# fpga_power.net
KiCad netlist of a schematic drawn in Altium Designer
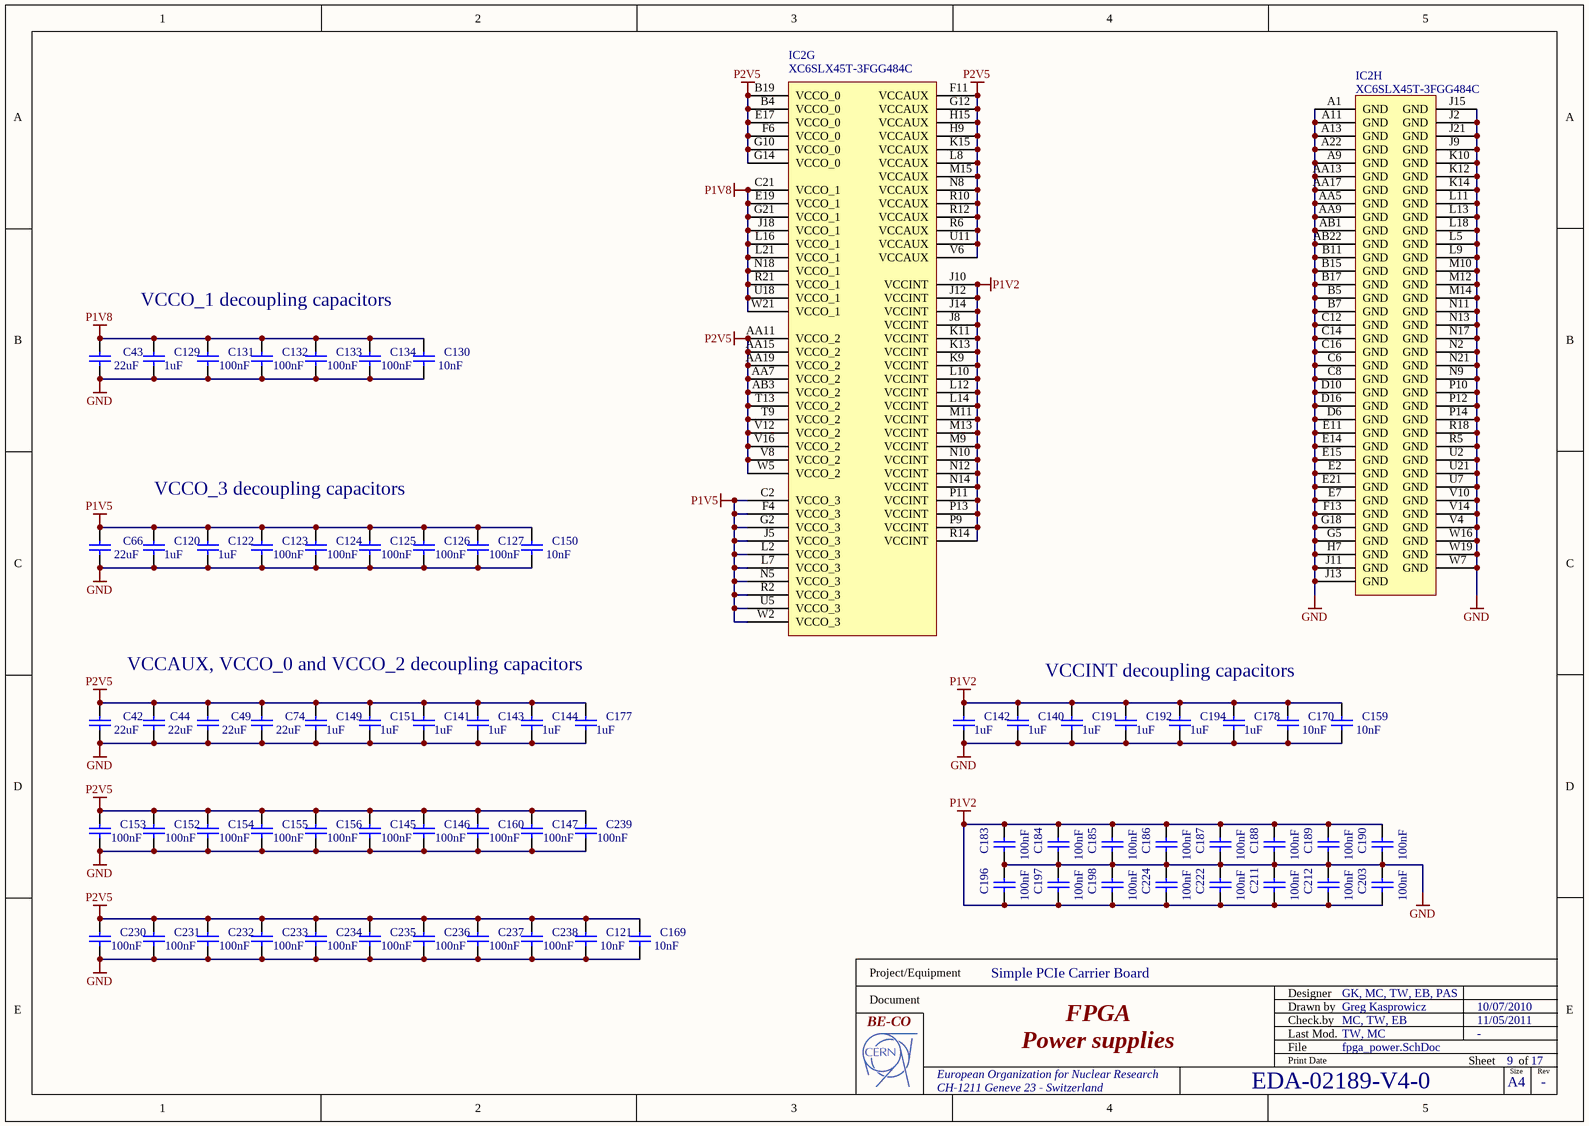
[diagram p0: fpga_power.SchDoc]

(export (version "E")
  (design (tool "Eeschema 10.0.6"))
  (components
    (comp (ref "C42")
      (value "22uF")
      (footprint "CAPC3216X180N")
      (description "Non-polarised capacitor")
      (fields
        (field (name "PART NUMBER") "CC1206_22UF_10V_10%_X7R")
        (field (name "VOLTAGE") "10V")
        (field (name "AUTHOR") "CERN DEM JLC")
      )
      (libsource (lib "Capacitors") (part "Capacitor - non polarized"))
    )
    (comp (ref "C43")
      (value "22uF")
      (footprint "CAPC3216X180N")
      (description "Non-polarised capacitor")
      (fields
        (field (name "PART NUMBER") "CC1206_22UF_10V_10%_X7R")
        (field (name "VOLTAGE") "10V")
        (field (name "AUTHOR") "CERN DEM JLC")
      )
      (libsource (lib "Capacitors") (part "Capacitor - non polarized"))
    )
    (comp (ref "C44")
      (value "22uF")
      (footprint "CAPC3216X180N")
      (description "Non-polarised capacitor")
      (fields
        (field (name "PART NUMBER") "CC1206_22UF_10V_10%_X7R")
        (field (name "VOLTAGE") "10V")
        (field (name "AUTHOR") "CERN DEM JLC")
      )
      (libsource (lib "Capacitors") (part "Capacitor - non polarized"))
    )
    (comp (ref "C49")
      (value "22uF")
      (footprint "CAPC3216X180N")
      (description "Non-polarised capacitor")
      (fields
        (field (name "PART NUMBER") "CC1206_22UF_10V_10%_X7R")
        (field (name "VOLTAGE") "10V")
        (field (name "AUTHOR") "CERN DEM JLC")
      )
      (libsource (lib "Capacitors") (part "Capacitor - non polarized"))
    )
    (comp (ref "C66")
      (value "22uF")
      (footprint "CAPC3216X180N")
      (description "Non-polarised capacitor")
      (fields
        (field (name "PART NUMBER") "CC1206_22UF_10V_10%_X7R")
        (field (name "VOLTAGE") "10V")
        (field (name "AUTHOR") "CERN DEM JLC")
      )
      (libsource (lib "Capacitors") (part "Capacitor - non polarized"))
    )
    (comp (ref "C74")
      (value "22uF")
      (footprint "CAPC3216X180N")
      (description "Non-polarised capacitor")
      (fields
        (field (name "PART NUMBER") "CC1206_22UF_10V_10%_X7R")
        (field (name "VOLTAGE") "10V")
        (field (name "AUTHOR") "CERN DEM JLC")
      )
      (libsource (lib "Capacitors") (part "Capacitor - non polarized"))
    )
    (comp (ref "C120")
      (value "1uF")
      (footprint "CAPC1608X87N")
      (description "Non-polarised capacitor")
      (fields
        (field (name "PART NUMBER") "CC0603_1UF_16V_10%_X7R")
        (field (name "VOLTAGE") "16V")
        (field (name "AUTHOR") "CERN DEM JLC")
      )
      (libsource (lib "Capacitors") (part "Capacitor - non polarized"))
    )
    (comp (ref "C121")
      (value "10nF")
      (footprint "CAPC1608X87N")
      (description "Non-polarised capacitor")
      (fields
        (field (name "PART NUMBER") "CC0603_10NF_50V_10%_X7R")
        (field (name "VOLTAGE") "50V")
        (field (name "AUTHOR") "CERN DEM JLC")
      )
      (libsource (lib "Capacitors") (part "Capacitor - non polarized"))
    )
    (comp (ref "C122")
      (value "1uF")
      (footprint "CAPC1608X87N")
      (description "Non-polarised capacitor")
      (fields
        (field (name "PART NUMBER") "CC0603_1UF_16V_10%_X7R")
        (field (name "VOLTAGE") "16V")
        (field (name "AUTHOR") "CERN DEM JLC")
      )
      (libsource (lib "Capacitors") (part "Capacitor - non polarized"))
    )
    (comp (ref "C123")
      (value "100nF")
      (footprint "CAPC1005X55N")
      (description "Non-polarised capacitor")
      (fields
        (field (name "PART NUMBER") "CC0402_100NF_16V_10%_X7R")
        (field (name "VOLTAGE") "16V")
        (field (name "AUTHOR") "CERN DEM JLC")
      )
      (libsource (lib "Capacitors") (part "Capacitor - non polarized"))
    )
    (comp (ref "C124")
      (value "100nF")
      (footprint "CAPC1005X55N")
      (description "Non-polarised capacitor")
      (fields
        (field (name "PART NUMBER") "CC0402_100NF_16V_10%_X7R")
        (field (name "VOLTAGE") "16V")
        (field (name "AUTHOR") "CERN DEM JLC")
      )
      (libsource (lib "Capacitors") (part "Capacitor - non polarized"))
    )
    (comp (ref "C125")
      (value "100nF")
      (footprint "CAPC1005X55N")
      (description "Non-polarised capacitor")
      (fields
        (field (name "PART NUMBER") "CC0402_100NF_16V_10%_X7R")
        (field (name "VOLTAGE") "16V")
        (field (name "AUTHOR") "CERN DEM JLC")
      )
      (libsource (lib "Capacitors") (part "Capacitor - non polarized"))
    )
    (comp (ref "C126")
      (value "100nF")
      (footprint "CAPC1005X55N")
      (description "Non-polarised capacitor")
      (fields
        (field (name "PART NUMBER") "CC0402_100NF_16V_10%_X7R")
        (field (name "VOLTAGE") "16V")
        (field (name "AUTHOR") "CERN DEM JLC")
      )
      (libsource (lib "Capacitors") (part "Capacitor - non polarized"))
    )
    (comp (ref "C127")
      (value "100nF")
      (footprint "CAPC1005X55N")
      (description "Non-polarised capacitor")
      (fields
        (field (name "PART NUMBER") "CC0402_100NF_16V_10%_X7R")
        (field (name "VOLTAGE") "16V")
        (field (name "AUTHOR") "CERN DEM JLC")
      )
      (libsource (lib "Capacitors") (part "Capacitor - non polarized"))
    )
    (comp (ref "C129")
      (value "1uF")
      (footprint "CAPC1608X87N")
      (description "Non-polarised capacitor")
      (fields
        (field (name "PART NUMBER") "CC0603_1UF_16V_10%_X7R")
        (field (name "VOLTAGE") "16V")
        (field (name "AUTHOR") "CERN DEM JLC")
      )
      (libsource (lib "Capacitors") (part "Capacitor - non polarized"))
    )
    (comp (ref "C130")
      (value "10nF")
      (footprint "CAPC1608X87N")
      (description "Non-polarised capacitor")
      (fields
        (field (name "PART NUMBER") "CC0603_10NF_50V_10%_X7R")
        (field (name "VOLTAGE") "50V")
        (field (name "AUTHOR") "CERN DEM JLC")
      )
      (libsource (lib "Capacitors") (part "Capacitor - non polarized"))
    )
    (comp (ref "C131")
      (value "100nF")
      (footprint "CAPC1005X55N")
      (description "Non-polarised capacitor")
      (fields
        (field (name "PART NUMBER") "CC0402_100NF_16V_10%_X7R")
        (field (name "VOLTAGE") "16V")
        (field (name "AUTHOR") "CERN DEM JLC")
      )
      (libsource (lib "Capacitors") (part "Capacitor - non polarized"))
    )
    (comp (ref "C132")
      (value "100nF")
      (footprint "CAPC1005X55N")
      (description "Non-polarised capacitor")
      (fields
        (field (name "PART NUMBER") "CC0402_100NF_16V_10%_X7R")
        (field (name "VOLTAGE") "16V")
        (field (name "AUTHOR") "CERN DEM JLC")
      )
      (libsource (lib "Capacitors") (part "Capacitor - non polarized"))
    )
    (comp (ref "C133")
      (value "100nF")
      (footprint "CAPC1005X55N")
      (description "Non-polarised capacitor")
      (fields
        (field (name "PART NUMBER") "CC0402_100NF_16V_10%_X7R")
        (field (name "VOLTAGE") "16V")
        (field (name "AUTHOR") "CERN DEM JLC")
      )
      (libsource (lib "Capacitors") (part "Capacitor - non polarized"))
    )
    (comp (ref "C134")
      (value "100nF")
      (footprint "CAPC1005X55N")
      (description "Non-polarised capacitor")
      (fields
        (field (name "PART NUMBER") "CC0402_100NF_16V_10%_X7R")
        (field (name "VOLTAGE") "16V")
        (field (name "AUTHOR") "CERN DEM JLC")
      )
      (libsource (lib "Capacitors") (part "Capacitor - non polarized"))
    )
    (comp (ref "C140")
      (value "1uF")
      (footprint "CAPC1608X87N")
      (description "Non-polarised capacitor")
      (fields
        (field (name "PART NUMBER") "CC0603_1UF_16V_10%_X7R")
        (field (name "VOLTAGE") "16V")
        (field (name "AUTHOR") "CERN DEM JLC")
      )
      (libsource (lib "Capacitors") (part "Capacitor - non polarized"))
    )
    (comp (ref "C141")
      (value "1uF")
      (footprint "CAPC1608X87N")
      (description "Non-polarised capacitor")
      (fields
        (field (name "PART NUMBER") "CC0603_1UF_16V_10%_X7R")
        (field (name "VOLTAGE") "16V")
        (field (name "AUTHOR") "CERN DEM JLC")
      )
      (libsource (lib "Capacitors") (part "Capacitor - non polarized"))
    )
    (comp (ref "C142")
      (value "1uF")
      (footprint "CAPC1608X87N")
      (description "Non-polarised capacitor")
      (fields
        (field (name "PART NUMBER") "CC0603_1UF_16V_10%_X7R")
        (field (name "VOLTAGE") "16V")
        (field (name "AUTHOR") "CERN DEM JLC")
      )
      (libsource (lib "Capacitors") (part "Capacitor - non polarized"))
    )
    (comp (ref "C143")
      (value "1uF")
      (footprint "CAPC1608X87N")
      (description "Non-polarised capacitor")
      (fields
        (field (name "PART NUMBER") "CC0603_1UF_16V_10%_X7R")
        (field (name "VOLTAGE") "16V")
        (field (name "AUTHOR") "CERN DEM JLC")
      )
      (libsource (lib "Capacitors") (part "Capacitor - non polarized"))
    )
    (comp (ref "C144")
      (value "1uF")
      (footprint "CAPC1608X87N")
      (description "Non-polarised capacitor")
      (fields
        (field (name "PART NUMBER") "CC0603_1UF_16V_10%_X7R")
        (field (name "VOLTAGE") "16V")
        (field (name "AUTHOR") "CERN DEM JLC")
      )
      (libsource (lib "Capacitors") (part "Capacitor - non polarized"))
    )
    (comp (ref "C145")
      (value "100nF")
      (footprint "CAPC1005X55N")
      (description "Non-polarised capacitor")
      (fields
        (field (name "PART NUMBER") "CC0402_100NF_16V_10%_X7R")
        (field (name "VOLTAGE") "16V")
        (field (name "AUTHOR") "CERN DEM JLC")
      )
      (libsource (lib "Capacitors") (part "Capacitor - non polarized"))
    )
    (comp (ref "C146")
      (value "100nF")
      (footprint "CAPC1005X55N")
      (description "Non-polarised capacitor")
      (fields
        (field (name "PART NUMBER") "CC0402_100NF_16V_10%_X7R")
        (field (name "VOLTAGE") "16V")
        (field (name "AUTHOR") "CERN DEM JLC")
      )
      (libsource (lib "Capacitors") (part "Capacitor - non polarized"))
    )
    (comp (ref "C147")
      (value "100nF")
      (footprint "CAPC1005X55N")
      (description "Non-polarised capacitor")
      (fields
        (field (name "PART NUMBER") "CC0402_100NF_16V_10%_X7R")
        (field (name "VOLTAGE") "16V")
        (field (name "AUTHOR") "CERN DEM JLC")
      )
      (libsource (lib "Capacitors") (part "Capacitor - non polarized"))
    )
    (comp (ref "C149")
      (value "1uF")
      (footprint "CAPC1608X87N")
      (description "Non-polarised capacitor")
      (fields
        (field (name "PART NUMBER") "CC0603_1UF_16V_10%_X7R")
        (field (name "VOLTAGE") "16V")
        (field (name "AUTHOR") "CERN DEM JLC")
      )
      (libsource (lib "Capacitors") (part "Capacitor - non polarized"))
    )
    (comp (ref "C150")
      (value "10nF")
      (footprint "CAPC1608X87N")
      (description "Non-polarised capacitor")
      (fields
        (field (name "PART NUMBER") "CC0603_10NF_50V_10%_X7R")
        (field (name "VOLTAGE") "50V")
        (field (name "AUTHOR") "CERN DEM JLC")
      )
      (libsource (lib "Capacitors") (part "Capacitor - non polarized"))
    )
    (comp (ref "C151")
      (value "1uF")
      (footprint "CAPC1608X87N")
      (description "Non-polarised capacitor")
      (fields
        (field (name "PART NUMBER") "CC0603_1UF_16V_10%_X7R")
        (field (name "VOLTAGE") "16V")
        (field (name "AUTHOR") "CERN DEM JLC")
      )
      (libsource (lib "Capacitors") (part "Capacitor - non polarized"))
    )
    (comp (ref "C152")
      (value "100nF")
      (footprint "CAPC1005X55N")
      (description "Non-polarised capacitor")
      (fields
        (field (name "PART NUMBER") "CC0402_100NF_16V_10%_X7R")
        (field (name "VOLTAGE") "16V")
        (field (name "AUTHOR") "CERN DEM JLC")
      )
      (libsource (lib "Capacitors") (part "Capacitor - non polarized"))
    )
    (comp (ref "C153")
      (value "100nF")
      (footprint "CAPC1005X55N")
      (description "Non-polarised capacitor")
      (fields
        (field (name "PART NUMBER") "CC0402_100NF_16V_10%_X7R")
        (field (name "VOLTAGE") "16V")
        (field (name "AUTHOR") "CERN DEM JLC")
      )
      (libsource (lib "Capacitors") (part "Capacitor - non polarized"))
    )
    (comp (ref "C154")
      (value "100nF")
      (footprint "CAPC1005X55N")
      (description "Non-polarised capacitor")
      (fields
        (field (name "PART NUMBER") "CC0402_100NF_16V_10%_X7R")
        (field (name "VOLTAGE") "16V")
        (field (name "AUTHOR") "CERN DEM JLC")
      )
      (libsource (lib "Capacitors") (part "Capacitor - non polarized"))
    )
    (comp (ref "C155")
      (value "100nF")
      (footprint "CAPC1005X55N")
      (description "Non-polarised capacitor")
      (fields
        (field (name "PART NUMBER") "CC0402_100NF_16V_10%_X7R")
        (field (name "VOLTAGE") "16V")
        (field (name "AUTHOR") "CERN DEM JLC")
      )
      (libsource (lib "Capacitors") (part "Capacitor - non polarized"))
    )
    (comp (ref "C156")
      (value "100nF")
      (footprint "CAPC1005X55N")
      (description "Non-polarised capacitor")
      (fields
        (field (name "PART NUMBER") "CC0402_100NF_16V_10%_X7R")
        (field (name "VOLTAGE") "16V")
        (field (name "AUTHOR") "CERN DEM JLC")
      )
      (libsource (lib "Capacitors") (part "Capacitor - non polarized"))
    )
    (comp (ref "C159")
      (value "10nF")
      (footprint "CAPC1608X87N")
      (description "Non-polarised capacitor")
      (fields
        (field (name "PART NUMBER") "CC0603_10NF_50V_10%_X7R")
        (field (name "VOLTAGE") "50V")
        (field (name "AUTHOR") "CERN DEM JLC")
      )
      (libsource (lib "Capacitors") (part "Capacitor - non polarized"))
    )
    (comp (ref "C160")
      (value "100nF")
      (footprint "CAPC1005X55N")
      (description "Non-polarised capacitor")
      (fields
        (field (name "PART NUMBER") "CC0402_100NF_16V_10%_X7R")
        (field (name "VOLTAGE") "16V")
        (field (name "AUTHOR") "CERN DEM JLC")
      )
      (libsource (lib "Capacitors") (part "Capacitor - non polarized"))
    )
    (comp (ref "C169")
      (value "10nF")
      (footprint "CAPC1608X87N")
      (description "Non-polarised capacitor")
      (fields
        (field (name "PART NUMBER") "CC0603_10NF_50V_10%_X7R")
        (field (name "VOLTAGE") "50V")
        (field (name "AUTHOR") "CERN DEM JLC")
      )
      (libsource (lib "Capacitors") (part "Capacitor - non polarized"))
    )
    (comp (ref "C170")
      (value "10nF")
      (footprint "CAPC1608X87N")
      (description "Non-polarised capacitor")
      (fields
        (field (name "PART NUMBER") "CC0603_10NF_50V_10%_X7R")
        (field (name "VOLTAGE") "50V")
        (field (name "AUTHOR") "CERN DEM JLC")
      )
      (libsource (lib "Capacitors") (part "Capacitor - non polarized"))
    )
    (comp (ref "C177")
      (value "1uF")
      (footprint "CAPC1608X87N")
      (description "Non-polarised capacitor")
      (fields
        (field (name "PART NUMBER") "CC0603_1UF_16V_10%_X7R")
        (field (name "VOLTAGE") "16V")
        (field (name "AUTHOR") "CERN DEM JLC")
      )
      (libsource (lib "Capacitors") (part "Capacitor - non polarized"))
    )
    (comp (ref "C178")
      (value "1uF")
      (footprint "CAPC1608X87N")
      (description "Non-polarised capacitor")
      (fields
        (field (name "PART NUMBER") "CC0603_1UF_16V_10%_X7R")
        (field (name "VOLTAGE") "16V")
        (field (name "AUTHOR") "CERN DEM JLC")
      )
      (libsource (lib "Capacitors") (part "Capacitor - non polarized"))
    )
    (comp (ref "C183")
      (value "100nF")
      (footprint "CAPC1005X55N")
      (description "Non-polarised capacitor")
      (fields
        (field (name "PART NUMBER") "CC0402_100NF_16V_10%_X7R")
        (field (name "VOLTAGE") "16V")
        (field (name "AUTHOR") "CERN DEM JLC")
      )
      (libsource (lib "Capacitors") (part "Capacitor - non polarized"))
    )
    (comp (ref "C184")
      (value "100nF")
      (footprint "CAPC1005X55N")
      (description "Non-polarised capacitor")
      (fields
        (field (name "PART NUMBER") "CC0402_100NF_16V_10%_X7R")
        (field (name "VOLTAGE") "16V")
        (field (name "AUTHOR") "CERN DEM JLC")
      )
      (libsource (lib "Capacitors") (part "Capacitor - non polarized"))
    )
    (comp (ref "C185")
      (value "100nF")
      (footprint "CAPC1005X55N")
      (description "Non-polarised capacitor")
      (fields
        (field (name "PART NUMBER") "CC0402_100NF_16V_10%_X7R")
        (field (name "VOLTAGE") "16V")
        (field (name "AUTHOR") "CERN DEM JLC")
      )
      (libsource (lib "Capacitors") (part "Capacitor - non polarized"))
    )
    (comp (ref "C186")
      (value "100nF")
      (footprint "CAPC1005X55N")
      (description "Non-polarised capacitor")
      (fields
        (field (name "PART NUMBER") "CC0402_100NF_16V_10%_X7R")
        (field (name "VOLTAGE") "16V")
        (field (name "AUTHOR") "CERN DEM JLC")
      )
      (libsource (lib "Capacitors") (part "Capacitor - non polarized"))
    )
    (comp (ref "C187")
      (value "100nF")
      (footprint "CAPC1005X55N")
      (description "Non-polarised capacitor")
      (fields
        (field (name "PART NUMBER") "CC0402_100NF_16V_10%_X7R")
        (field (name "VOLTAGE") "16V")
        (field (name "AUTHOR") "CERN DEM JLC")
      )
      (libsource (lib "Capacitors") (part "Capacitor - non polarized"))
    )
    (comp (ref "C188")
      (value "100nF")
      (footprint "CAPC1005X55N")
      (description "Non-polarised capacitor")
      (fields
        (field (name "PART NUMBER") "CC0402_100NF_16V_10%_X7R")
        (field (name "VOLTAGE") "16V")
        (field (name "AUTHOR") "CERN DEM JLC")
      )
      (libsource (lib "Capacitors") (part "Capacitor - non polarized"))
    )
    (comp (ref "C189")
      (value "100nF")
      (footprint "CAPC1005X55N")
      (description "Non-polarised capacitor")
      (fields
        (field (name "PART NUMBER") "CC0402_100NF_16V_10%_X7R")
        (field (name "VOLTAGE") "16V")
        (field (name "AUTHOR") "CERN DEM JLC")
      )
      (libsource (lib "Capacitors") (part "Capacitor - non polarized"))
    )
    (comp (ref "C190")
      (value "100nF")
      (footprint "CAPC1005X55N")
      (description "Non-polarised capacitor")
      (fields
        (field (name "PART NUMBER") "CC0402_100NF_16V_10%_X7R")
        (field (name "VOLTAGE") "16V")
        (field (name "AUTHOR") "CERN DEM JLC")
      )
      (libsource (lib "Capacitors") (part "Capacitor - non polarized"))
    )
    (comp (ref "C191")
      (value "1uF")
      (footprint "CAPC1608X87N")
      (description "Non-polarised capacitor")
      (fields
        (field (name "PART NUMBER") "CC0603_1UF_16V_10%_X7R")
        (field (name "VOLTAGE") "16V")
        (field (name "AUTHOR") "CERN DEM JLC")
      )
      (libsource (lib "Capacitors") (part "Capacitor - non polarized"))
    )
    (comp (ref "C192")
      (value "1uF")
      (footprint "CAPC1608X87N")
      (description "Non-polarised capacitor")
      (fields
        (field (name "PART NUMBER") "CC0603_1UF_16V_10%_X7R")
        (field (name "VOLTAGE") "16V")
        (field (name "AUTHOR") "CERN DEM JLC")
      )
      (libsource (lib "Capacitors") (part "Capacitor - non polarized"))
    )
    (comp (ref "C194")
      (value "1uF")
      (footprint "CAPC1608X87N")
      (description "Non-polarised capacitor")
      (fields
        (field (name "PART NUMBER") "CC0603_1UF_16V_10%_X7R")
        (field (name "VOLTAGE") "16V")
        (field (name "AUTHOR") "CERN DEM JLC")
      )
      (libsource (lib "Capacitors") (part "Capacitor - non polarized"))
    )
    (comp (ref "C196")
      (value "100nF")
      (footprint "CAPC1005X55N")
      (description "Non-polarised capacitor")
      (fields
        (field (name "PART NUMBER") "CC0402_100NF_16V_10%_X7R")
        (field (name "VOLTAGE") "16V")
        (field (name "AUTHOR") "CERN DEM JLC")
      )
      (libsource (lib "Capacitors") (part "Capacitor - non polarized"))
    )
    (comp (ref "C197")
      (value "100nF")
      (footprint "CAPC1005X55N")
      (description "Non-polarised capacitor")
      (fields
        (field (name "PART NUMBER") "CC0402_100NF_16V_10%_X7R")
        (field (name "VOLTAGE") "16V")
        (field (name "AUTHOR") "CERN DEM JLC")
      )
      (libsource (lib "Capacitors") (part "Capacitor - non polarized"))
    )
    (comp (ref "C198")
      (value "100nF")
      (footprint "CAPC1005X55N")
      (description "Non-polarised capacitor")
      (fields
        (field (name "PART NUMBER") "CC0402_100NF_16V_10%_X7R")
        (field (name "VOLTAGE") "16V")
        (field (name "AUTHOR") "CERN DEM JLC")
      )
      (libsource (lib "Capacitors") (part "Capacitor - non polarized"))
    )
    (comp (ref "C203")
      (value "100nF")
      (footprint "CAPC1005X55N")
      (description "Non-polarised capacitor")
      (fields
        (field (name "PART NUMBER") "CC0402_100NF_16V_10%_X7R")
        (field (name "VOLTAGE") "16V")
        (field (name "AUTHOR") "CERN DEM JLC")
      )
      (libsource (lib "Capacitors") (part "Capacitor - non polarized"))
    )
    (comp (ref "C211")
      (value "100nF")
      (footprint "CAPC1005X55N")
      (description "Non-polarised capacitor")
      (fields
        (field (name "PART NUMBER") "CC0402_100NF_16V_10%_X7R")
        (field (name "VOLTAGE") "16V")
        (field (name "AUTHOR") "CERN DEM JLC")
      )
      (libsource (lib "Capacitors") (part "Capacitor - non polarized"))
    )
    (comp (ref "C212")
      (value "100nF")
      (footprint "CAPC1005X55N")
      (description "Non-polarised capacitor")
      (fields
        (field (name "PART NUMBER") "CC0402_100NF_16V_10%_X7R")
        (field (name "VOLTAGE") "16V")
        (field (name "AUTHOR") "CERN DEM JLC")
      )
      (libsource (lib "Capacitors") (part "Capacitor - non polarized"))
    )
    (comp (ref "C222")
      (value "100nF")
      (footprint "CAPC1005X55N")
      (description "Non-polarised capacitor")
      (fields
        (field (name "PART NUMBER") "CC0402_100NF_16V_10%_X7R")
        (field (name "VOLTAGE") "16V")
        (field (name "AUTHOR") "CERN DEM JLC")
      )
      (libsource (lib "Capacitors") (part "Capacitor - non polarized"))
    )
    (comp (ref "C224")
      (value "100nF")
      (footprint "CAPC1005X55N")
      (description "Non-polarised capacitor")
      (fields
        (field (name "PART NUMBER") "CC0402_100NF_16V_10%_X7R")
        (field (name "VOLTAGE") "16V")
        (field (name "AUTHOR") "CERN DEM JLC")
      )
      (libsource (lib "Capacitors") (part "Capacitor - non polarized"))
    )
    (comp (ref "C230")
      (value "100nF")
      (footprint "CAPC1005X55N")
      (description "Non-polarised capacitor")
      (fields
        (field (name "PART NUMBER") "CC0402_100NF_16V_10%_X7R")
        (field (name "VOLTAGE") "16V")
        (field (name "AUTHOR") "CERN DEM JLC")
      )
      (libsource (lib "Capacitors") (part "Capacitor - non polarized"))
    )
    (comp (ref "C231")
      (value "100nF")
      (footprint "CAPC1005X55N")
      (description "Non-polarised capacitor")
      (fields
        (field (name "PART NUMBER") "CC0402_100NF_16V_10%_X7R")
        (field (name "VOLTAGE") "16V")
        (field (name "AUTHOR") "CERN DEM JLC")
      )
      (libsource (lib "Capacitors") (part "Capacitor - non polarized"))
    )
    (comp (ref "C232")
      (value "100nF")
      (footprint "CAPC1005X55N")
      (description "Non-polarised capacitor")
      (fields
        (field (name "PART NUMBER") "CC0402_100NF_16V_10%_X7R")
        (field (name "VOLTAGE") "16V")
        (field (name "AUTHOR") "CERN DEM JLC")
      )
      (libsource (lib "Capacitors") (part "Capacitor - non polarized"))
    )
    (comp (ref "C233")
      (value "100nF")
      (footprint "CAPC1005X55N")
      (description "Non-polarised capacitor")
      (fields
        (field (name "PART NUMBER") "CC0402_100NF_16V_10%_X7R")
        (field (name "VOLTAGE") "16V")
        (field (name "AUTHOR") "CERN DEM JLC")
      )
      (libsource (lib "Capacitors") (part "Capacitor - non polarized"))
    )
    (comp (ref "C234")
      (value "100nF")
      (footprint "CAPC1005X55N")
      (description "Non-polarised capacitor")
      (fields
        (field (name "PART NUMBER") "CC0402_100NF_16V_10%_X7R")
        (field (name "VOLTAGE") "16V")
        (field (name "AUTHOR") "CERN DEM JLC")
      )
      (libsource (lib "Capacitors") (part "Capacitor - non polarized"))
    )
    (comp (ref "C235")
      (value "100nF")
      (footprint "CAPC1005X55N")
      (description "Non-polarised capacitor")
      (fields
        (field (name "PART NUMBER") "CC0402_100NF_16V_10%_X7R")
        (field (name "VOLTAGE") "16V")
        (field (name "AUTHOR") "CERN DEM JLC")
      )
      (libsource (lib "Capacitors") (part "Capacitor - non polarized"))
    )
    (comp (ref "C236")
      (value "100nF")
      (footprint "CAPC1005X55N")
      (description "Non-polarised capacitor")
      (fields
        (field (name "PART NUMBER") "CC0402_100NF_16V_10%_X7R")
        (field (name "VOLTAGE") "16V")
        (field (name "AUTHOR") "CERN DEM JLC")
      )
      (libsource (lib "Capacitors") (part "Capacitor - non polarized"))
    )
    (comp (ref "C237")
      (value "100nF")
      (footprint "CAPC1005X55N")
      (description "Non-polarised capacitor")
      (fields
        (field (name "PART NUMBER") "CC0402_100NF_16V_10%_X7R")
        (field (name "VOLTAGE") "16V")
        (field (name "AUTHOR") "CERN DEM JLC")
      )
      (libsource (lib "Capacitors") (part "Capacitor - non polarized"))
    )
    (comp (ref "C238")
      (value "100nF")
      (footprint "CAPC1005X55N")
      (description "Non-polarised capacitor")
      (fields
        (field (name "PART NUMBER") "CC0402_100NF_16V_10%_X7R")
        (field (name "VOLTAGE") "16V")
        (field (name "AUTHOR") "CERN DEM JLC")
      )
      (libsource (lib "Capacitors") (part "Capacitor - non polarized"))
    )
    (comp (ref "C239")
      (value "100nF")
      (footprint "CAPC1005X55N")
      (description "Non-polarised capacitor")
      (fields
        (field (name "PART NUMBER") "CC0402_100NF_16V_10%_X7R")
        (field (name "VOLTAGE") "16V")
        (field (name "AUTHOR") "CERN DEM JLC")
      )
      (libsource (lib "Capacitors") (part "Capacitor - non polarized"))
    )
    (comp (ref "IC2")
      (value "XC6SLX45T-3FGG484C")
      (footprint "BGA484C100P22X22_2300X2300X260")
      (fields (field (name "MANUFACTURER") "XILINX") (field (name "AUTHOR") "CERN DEM JLC"))
      (libsource (lib "ICs And Semiconductors") (part "XC6SLX45T-3FGG484C"))
    )
  )
  (nets
    (net (code "1") (name "GND") (class "Default")
      (node (ref "C120") (pin "1") (pinfunction "1_1") (pintype "passive"))
      (node (ref "C121") (pin "1") (pinfunction "1_1") (pintype "passive"))
      (node (ref "C122") (pin "1") (pinfunction "1_1") (pintype "passive"))
      (node (ref "C123") (pin "1") (pinfunction "1_1") (pintype "passive"))
      (node (ref "C124") (pin "1") (pinfunction "1_1") (pintype "passive"))
      (node (ref "C125") (pin "1") (pinfunction "1_1") (pintype "passive"))
      (node (ref "C126") (pin "1") (pinfunction "1_1") (pintype "passive"))
      (node (ref "C127") (pin "1") (pinfunction "1_1") (pintype "passive"))
      (node (ref "C129") (pin "1") (pinfunction "1_1") (pintype "passive"))
      (node (ref "C130") (pin "1") (pinfunction "1_1") (pintype "passive"))
      (node (ref "C131") (pin "1") (pinfunction "1_1") (pintype "passive"))
      (node (ref "C132") (pin "1") (pinfunction "1_1") (pintype "passive"))
      (node (ref "C133") (pin "1") (pinfunction "1_1") (pintype "passive"))
      (node (ref "C134") (pin "1") (pinfunction "1_1") (pintype "passive"))
      (node (ref "C140") (pin "2") (pinfunction "2_2") (pintype "passive"))
      (node (ref "C141") (pin "1") (pinfunction "1_1") (pintype "passive"))
      (node (ref "C142") (pin "2") (pinfunction "2_2") (pintype "passive"))
      (node (ref "C143") (pin "1") (pinfunction "1_1") (pintype "passive"))
      (node (ref "C144") (pin "1") (pinfunction "1_1") (pintype "passive"))
      (node (ref "C145") (pin "1") (pinfunction "1_1") (pintype "passive"))
      (node (ref "C146") (pin "1") (pinfunction "1_1") (pintype "passive"))
      (node (ref "C147") (pin "1") (pinfunction "1_1") (pintype "passive"))
      (node (ref "C149") (pin "1") (pinfunction "1_1") (pintype "passive"))
      (node (ref "C150") (pin "1") (pinfunction "1_1") (pintype "passive"))
      (node (ref "C151") (pin "1") (pinfunction "1_1") (pintype "passive"))
      (node (ref "C152") (pin "1") (pinfunction "1_1") (pintype "passive"))
      (node (ref "C153") (pin "1") (pinfunction "1_1") (pintype "passive"))
      (node (ref "C154") (pin "1") (pinfunction "1_1") (pintype "passive"))
      (node (ref "C155") (pin "1") (pinfunction "1_1") (pintype "passive"))
      (node (ref "C156") (pin "1") (pinfunction "1_1") (pintype "passive"))
      (node (ref "C159") (pin "1") (pinfunction "1_1") (pintype "passive"))
      (node (ref "C160") (pin "1") (pinfunction "1_1") (pintype "passive"))
      (node (ref "C169") (pin "1") (pinfunction "1_1") (pintype "passive"))
      (node (ref "C170") (pin "1") (pinfunction "1_1") (pintype "passive"))
      (node (ref "C177") (pin "1") (pinfunction "1_1") (pintype "passive"))
      (node (ref "C178") (pin "1") (pinfunction "1_1") (pintype "passive"))
      (node (ref "C183") (pin "1") (pinfunction "1_1") (pintype "passive"))
      (node (ref "C184") (pin "1") (pinfunction "1_1") (pintype "passive"))
      (node (ref "C185") (pin "1") (pinfunction "1_1") (pintype "passive"))
      (node (ref "C186") (pin "1") (pinfunction "1_1") (pintype "passive"))
      (node (ref "C187") (pin "1") (pinfunction "1_1") (pintype "passive"))
      (node (ref "C188") (pin "1") (pinfunction "1_1") (pintype "passive"))
      (node (ref "C189") (pin "1") (pinfunction "1_1") (pintype "passive"))
      (node (ref "C190") (pin "1") (pinfunction "1_1") (pintype "passive"))
      (node (ref "C191") (pin "1") (pinfunction "1_1") (pintype "passive"))
      (node (ref "C192") (pin "1") (pinfunction "1_1") (pintype "passive"))
      (node (ref "C194") (pin "1") (pinfunction "1_1") (pintype "passive"))
      (node (ref "C196") (pin "2") (pinfunction "2_2") (pintype "passive"))
      (node (ref "C197") (pin "2") (pinfunction "2_2") (pintype "passive"))
      (node (ref "C198") (pin "2") (pinfunction "2_2") (pintype "passive"))
      (node (ref "C203") (pin "2") (pinfunction "2_2") (pintype "passive"))
      (node (ref "C211") (pin "2") (pinfunction "2_2") (pintype "passive"))
      (node (ref "C212") (pin "2") (pinfunction "2_2") (pintype "passive"))
      (node (ref "C222") (pin "2") (pinfunction "2_2") (pintype "passive"))
      (node (ref "C224") (pin "2") (pinfunction "2_2") (pintype "passive"))
      (node (ref "C230") (pin "1") (pinfunction "1_1") (pintype "passive"))
      (node (ref "C231") (pin "1") (pinfunction "1_1") (pintype "passive"))
      (node (ref "C232") (pin "1") (pinfunction "1_1") (pintype "passive"))
      (node (ref "C233") (pin "1") (pinfunction "1_1") (pintype "passive"))
      (node (ref "C234") (pin "1") (pinfunction "1_1") (pintype "passive"))
      (node (ref "C235") (pin "1") (pinfunction "1_1") (pintype "passive"))
      (node (ref "C236") (pin "1") (pinfunction "1_1") (pintype "passive"))
      (node (ref "C237") (pin "1") (pinfunction "1_1") (pintype "passive"))
      (node (ref "C238") (pin "1") (pinfunction "1_1") (pintype "passive"))
      (node (ref "C239") (pin "1") (pinfunction "1_1") (pintype "passive"))
      (node (ref "C42") (pin "1") (pinfunction "1_1") (pintype "passive"))
      (node (ref "C43") (pin "1") (pinfunction "1_1") (pintype "passive"))
      (node (ref "C44") (pin "1") (pinfunction "1_1") (pintype "passive"))
      (node (ref "C49") (pin "1") (pinfunction "1_1") (pintype "passive"))
      (node (ref "C66") (pin "1") (pinfunction "1_1") (pintype "passive"))
      (node (ref "C74") (pin "1") (pinfunction "1_1") (pintype "passive"))
      (node (ref "IC2") (pin "A1") (pinfunction "GND_A1") (pintype "power_in"))
      (node (ref "IC2") (pin "A11") (pinfunction "GND_A11") (pintype "power_in"))
      (node (ref "IC2") (pin "A13") (pinfunction "GND_A13") (pintype "power_in"))
      (node (ref "IC2") (pin "A22") (pinfunction "GND_A22") (pintype "power_in"))
      (node (ref "IC2") (pin "A9") (pinfunction "GND_A9") (pintype "power_in"))
      (node (ref "IC2") (pin "AA13") (pinfunction "GND_AA13") (pintype "power_in"))
      (node (ref "IC2") (pin "AA17") (pinfunction "GND_AA17") (pintype "power_in"))
      (node (ref "IC2") (pin "AA5") (pinfunction "GND_AA5") (pintype "power_in"))
      (node (ref "IC2") (pin "AA9") (pinfunction "GND_AA9") (pintype "power_in"))
      (node (ref "IC2") (pin "AB1") (pinfunction "GND_AB1") (pintype "power_in"))
      (node (ref "IC2") (pin "AB22") (pinfunction "GND_AB22") (pintype "power_in"))
      (node (ref "IC2") (pin "B11") (pinfunction "GND_B11") (pintype "power_in"))
      (node (ref "IC2") (pin "B15") (pinfunction "GND_B15") (pintype "power_in"))
      (node (ref "IC2") (pin "B17") (pinfunction "GND_B17") (pintype "power_in"))
      (node (ref "IC2") (pin "B5") (pinfunction "GND_B5") (pintype "power_in"))
      (node (ref "IC2") (pin "B7") (pinfunction "GND_B7") (pintype "power_in"))
      (node (ref "IC2") (pin "C12") (pinfunction "GND_C12") (pintype "power_in"))
      (node (ref "IC2") (pin "C14") (pinfunction "GND_C14") (pintype "power_in"))
      (node (ref "IC2") (pin "C16") (pinfunction "GND_C16") (pintype "power_in"))
      (node (ref "IC2") (pin "C6") (pinfunction "GND_C6") (pintype "power_in"))
      (node (ref "IC2") (pin "C8") (pinfunction "GND_C8") (pintype "power_in"))
      (node (ref "IC2") (pin "D10") (pinfunction "GND_D10") (pintype "power_in"))
      (node (ref "IC2") (pin "D16") (pinfunction "GND_D16") (pintype "power_in"))
      (node (ref "IC2") (pin "D6") (pinfunction "GND_D6") (pintype "power_in"))
      (node (ref "IC2") (pin "E11") (pinfunction "GND_E11") (pintype "power_in"))
      (node (ref "IC2") (pin "E14") (pinfunction "GND_E14") (pintype "power_in"))
      (node (ref "IC2") (pin "E15") (pinfunction "GND_E15") (pintype "power_in"))
      (node (ref "IC2") (pin "E2") (pinfunction "GND_E2") (pintype "power_in"))
      (node (ref "IC2") (pin "E21") (pinfunction "GND_E21") (pintype "power_in"))
      (node (ref "IC2") (pin "E7") (pinfunction "GND_E7") (pintype "power_in"))
      (node (ref "IC2") (pin "F13") (pinfunction "GND_F13") (pintype "power_in"))
      (node (ref "IC2") (pin "G18") (pinfunction "GND_G18") (pintype "power_in"))
      (node (ref "IC2") (pin "G5") (pinfunction "GND_G5") (pintype "power_in"))
      (node (ref "IC2") (pin "H7") (pinfunction "GND_H7") (pintype "power_in"))
      (node (ref "IC2") (pin "J11") (pinfunction "GND_J11") (pintype "power_in"))
      (node (ref "IC2") (pin "J13") (pinfunction "GND_J13") (pintype "power_in"))
      (node (ref "IC2") (pin "J15") (pinfunction "GND_J15") (pintype "power_in"))
      (node (ref "IC2") (pin "J2") (pinfunction "GND_J2") (pintype "power_in"))
      (node (ref "IC2") (pin "J21") (pinfunction "GND_J21") (pintype "power_in"))
      (node (ref "IC2") (pin "J9") (pinfunction "GND_J9") (pintype "power_in"))
      (node (ref "IC2") (pin "K10") (pinfunction "GND_K10") (pintype "power_in"))
      (node (ref "IC2") (pin "K12") (pinfunction "GND_K12") (pintype "power_in"))
      (node (ref "IC2") (pin "K14") (pinfunction "GND_K14") (pintype "power_in"))
      (node (ref "IC2") (pin "L11") (pinfunction "GND_L11") (pintype "power_in"))
      (node (ref "IC2") (pin "L13") (pinfunction "GND_L13") (pintype "power_in"))
      (node (ref "IC2") (pin "L18") (pinfunction "GND_L18") (pintype "power_in"))
      (node (ref "IC2") (pin "L5") (pinfunction "GND_L5") (pintype "power_in"))
      (node (ref "IC2") (pin "L9") (pinfunction "GND_L9") (pintype "power_in"))
      (node (ref "IC2") (pin "M10") (pinfunction "GND_M10") (pintype "power_in"))
      (node (ref "IC2") (pin "M12") (pinfunction "GND_M12") (pintype "power_in"))
      (node (ref "IC2") (pin "M14") (pinfunction "GND_M14") (pintype "power_in"))
      (node (ref "IC2") (pin "N11") (pinfunction "GND_N11") (pintype "power_in"))
      (node (ref "IC2") (pin "N13") (pinfunction "GND_N13") (pintype "power_in"))
      (node (ref "IC2") (pin "N17") (pinfunction "GND_N17") (pintype "power_in"))
      (node (ref "IC2") (pin "N2") (pinfunction "GND_N2") (pintype "power_in"))
      (node (ref "IC2") (pin "N21") (pinfunction "GND_N21") (pintype "power_in"))
      (node (ref "IC2") (pin "N9") (pinfunction "GND_N9") (pintype "power_in"))
      (node (ref "IC2") (pin "P10") (pinfunction "GND_P10") (pintype "power_in"))
      (node (ref "IC2") (pin "P12") (pinfunction "GND_P12") (pintype "power_in"))
      (node (ref "IC2") (pin "P14") (pinfunction "GND_P14") (pintype "power_in"))
      (node (ref "IC2") (pin "R18") (pinfunction "GND_R18") (pintype "power_in"))
      (node (ref "IC2") (pin "R5") (pinfunction "GND_R5") (pintype "power_in"))
      (node (ref "IC2") (pin "U2") (pinfunction "GND_U2") (pintype "power_in"))
      (node (ref "IC2") (pin "U21") (pinfunction "GND_U21") (pintype "power_in"))
      (node (ref "IC2") (pin "U7") (pinfunction "GND_U7") (pintype "power_in"))
      (node (ref "IC2") (pin "V10") (pinfunction "GND_V10") (pintype "power_in"))
      (node (ref "IC2") (pin "V14") (pinfunction "GND_V14") (pintype "power_in"))
      (node (ref "IC2") (pin "V4") (pinfunction "GND_V4") (pintype "power_in"))
      (node (ref "IC2") (pin "W16") (pinfunction "GND_W16") (pintype "power_in"))
      (node (ref "IC2") (pin "W19") (pinfunction "GND_W19") (pintype "power_in"))
      (node (ref "IC2") (pin "W7") (pinfunction "GND_W7") (pintype "power_in"))
    )
    (net (code "2") (name "P1V2") (class "Default")
      (node (ref "C140") (pin "1") (pinfunction "1_1") (pintype "passive"))
      (node (ref "C142") (pin "1") (pinfunction "1_1") (pintype "passive"))
      (node (ref "C159") (pin "2") (pinfunction "2_2") (pintype "passive"))
      (node (ref "C170") (pin "2") (pinfunction "2_2") (pintype "passive"))
      (node (ref "C178") (pin "2") (pinfunction "2_2") (pintype "passive"))
      (node (ref "C183") (pin "2") (pinfunction "2_2") (pintype "passive"))
      (node (ref "C184") (pin "2") (pinfunction "2_2") (pintype "passive"))
      (node (ref "C185") (pin "2") (pinfunction "2_2") (pintype "passive"))
      (node (ref "C186") (pin "2") (pinfunction "2_2") (pintype "passive"))
      (node (ref "C187") (pin "2") (pinfunction "2_2") (pintype "passive"))
      (node (ref "C188") (pin "2") (pinfunction "2_2") (pintype "passive"))
      (node (ref "C189") (pin "2") (pinfunction "2_2") (pintype "passive"))
      (node (ref "C190") (pin "2") (pinfunction "2_2") (pintype "passive"))
      (node (ref "C191") (pin "2") (pinfunction "2_2") (pintype "passive"))
      (node (ref "C192") (pin "2") (pinfunction "2_2") (pintype "passive"))
      (node (ref "C194") (pin "2") (pinfunction "2_2") (pintype "passive"))
      (node (ref "C196") (pin "1") (pinfunction "1_1") (pintype "passive"))
      (node (ref "C197") (pin "1") (pinfunction "1_1") (pintype "passive"))
      (node (ref "C198") (pin "1") (pinfunction "1_1") (pintype "passive"))
      (node (ref "C203") (pin "1") (pinfunction "1_1") (pintype "passive"))
      (node (ref "C211") (pin "1") (pinfunction "1_1") (pintype "passive"))
      (node (ref "C212") (pin "1") (pinfunction "1_1") (pintype "passive"))
      (node (ref "C222") (pin "1") (pinfunction "1_1") (pintype "passive"))
      (node (ref "C224") (pin "1") (pinfunction "1_1") (pintype "passive"))
      (node (ref "IC2") (pin "J10") (pinfunction "VCCINT_J10") (pintype "power_in"))
      (node (ref "IC2") (pin "J12") (pinfunction "VCCINT_J12") (pintype "power_in"))
      (node (ref "IC2") (pin "J14") (pinfunction "VCCINT_J14") (pintype "power_in"))
      (node (ref "IC2") (pin "J8") (pinfunction "VCCINT_J8") (pintype "power_in"))
      (node (ref "IC2") (pin "K11") (pinfunction "VCCINT_K11") (pintype "power_in"))
      (node (ref "IC2") (pin "K13") (pinfunction "VCCINT_K13") (pintype "power_in"))
      (node (ref "IC2") (pin "K9") (pinfunction "VCCINT_K9") (pintype "power_in"))
      (node (ref "IC2") (pin "L10") (pinfunction "VCCINT_L10") (pintype "power_in"))
      (node (ref "IC2") (pin "L12") (pinfunction "VCCINT_L12") (pintype "power_in"))
      (node (ref "IC2") (pin "L14") (pinfunction "VCCINT_L14") (pintype "power_in"))
      (node (ref "IC2") (pin "M11") (pinfunction "VCCINT_M11") (pintype "power_in"))
      (node (ref "IC2") (pin "M13") (pinfunction "VCCINT_M13") (pintype "power_in"))
      (node (ref "IC2") (pin "M9") (pinfunction "VCCINT_M9") (pintype "power_in"))
      (node (ref "IC2") (pin "N10") (pinfunction "VCCINT_N10") (pintype "power_in"))
      (node (ref "IC2") (pin "N12") (pinfunction "VCCINT_N12") (pintype "power_in"))
      (node (ref "IC2") (pin "N14") (pinfunction "VCCINT_N14") (pintype "power_in"))
      (node (ref "IC2") (pin "P11") (pinfunction "VCCINT_P11") (pintype "power_in"))
      (node (ref "IC2") (pin "P13") (pinfunction "VCCINT_P13") (pintype "power_in"))
      (node (ref "IC2") (pin "P9") (pinfunction "VCCINT_P9") (pintype "power_in"))
      (node (ref "IC2") (pin "R14") (pinfunction "VCCINT_R14") (pintype "power_in"))
    )
    (net (code "3") (name "P1V5") (class "Default")
      (node (ref "C120") (pin "2") (pinfunction "2_2") (pintype "passive"))
      (node (ref "C122") (pin "2") (pinfunction "2_2") (pintype "passive"))
      (node (ref "C123") (pin "2") (pinfunction "2_2") (pintype "passive"))
      (node (ref "C124") (pin "2") (pinfunction "2_2") (pintype "passive"))
      (node (ref "C125") (pin "2") (pinfunction "2_2") (pintype "passive"))
      (node (ref "C126") (pin "2") (pinfunction "2_2") (pintype "passive"))
      (node (ref "C127") (pin "2") (pinfunction "2_2") (pintype "passive"))
      (node (ref "C150") (pin "2") (pinfunction "2_2") (pintype "passive"))
      (node (ref "C66") (pin "2") (pinfunction "2_2") (pintype "passive"))
      (node (ref "IC2") (pin "C2") (pinfunction "VCCO_3_C2") (pintype "power_in"))
      (node (ref "IC2") (pin "F4") (pinfunction "VCCO_3_F4") (pintype "power_in"))
      (node (ref "IC2") (pin "G2") (pinfunction "VCCO_3_G2") (pintype "power_in"))
      (node (ref "IC2") (pin "J5") (pinfunction "VCCO_3_J5") (pintype "power_in"))
      (node (ref "IC2") (pin "L2") (pinfunction "VCCO_3_L2") (pintype "power_in"))
      (node (ref "IC2") (pin "L7") (pinfunction "VCCO_3_L7") (pintype "power_in"))
      (node (ref "IC2") (pin "N5") (pinfunction "VCCO_3_N5") (pintype "power_in"))
      (node (ref "IC2") (pin "R2") (pinfunction "VCCO_3_R2") (pintype "power_in"))
      (node (ref "IC2") (pin "U5") (pinfunction "VCCO_3_U5") (pintype "power_in"))
      (node (ref "IC2") (pin "W2") (pinfunction "VCCO_3_W2") (pintype "power_in"))
    )
    (net (code "4") (name "P1V8") (class "Default")
      (node (ref "C129") (pin "2") (pinfunction "2_2") (pintype "passive"))
      (node (ref "C130") (pin "2") (pinfunction "2_2") (pintype "passive"))
      (node (ref "C131") (pin "2") (pinfunction "2_2") (pintype "passive"))
      (node (ref "C132") (pin "2") (pinfunction "2_2") (pintype "passive"))
      (node (ref "C133") (pin "2") (pinfunction "2_2") (pintype "passive"))
      (node (ref "C134") (pin "2") (pinfunction "2_2") (pintype "passive"))
      (node (ref "C43") (pin "2") (pinfunction "2_2") (pintype "passive"))
      (node (ref "IC2") (pin "C21") (pinfunction "VCCO_1_C21") (pintype "power_in"))
      (node (ref "IC2") (pin "E19") (pinfunction "VCCO_1_E19") (pintype "power_in"))
      (node (ref "IC2") (pin "G21") (pinfunction "VCCO_1_G21") (pintype "power_in"))
      (node (ref "IC2") (pin "J18") (pinfunction "VCCO_1_J18") (pintype "power_in"))
      (node (ref "IC2") (pin "L16") (pinfunction "VCCO_1_L16") (pintype "power_in"))
      (node (ref "IC2") (pin "L21") (pinfunction "VCCO_1_L21") (pintype "power_in"))
      (node (ref "IC2") (pin "N18") (pinfunction "VCCO_1_N18") (pintype "power_in"))
      (node (ref "IC2") (pin "R21") (pinfunction "VCCO_1_R21") (pintype "power_in"))
      (node (ref "IC2") (pin "U18") (pinfunction "VCCO_1_U18") (pintype "power_in"))
      (node (ref "IC2") (pin "W21") (pinfunction "VCCO_1_W21") (pintype "power_in"))
    )
    (net (code "5") (name "P2V5") (class "Default")
      (node (ref "C121") (pin "2") (pinfunction "2_2") (pintype "passive"))
      (node (ref "C141") (pin "2") (pinfunction "2_2") (pintype "passive"))
      (node (ref "C143") (pin "2") (pinfunction "2_2") (pintype "passive"))
      (node (ref "C144") (pin "2") (pinfunction "2_2") (pintype "passive"))
      (node (ref "C145") (pin "2") (pinfunction "2_2") (pintype "passive"))
      (node (ref "C146") (pin "2") (pinfunction "2_2") (pintype "passive"))
      (node (ref "C147") (pin "2") (pinfunction "2_2") (pintype "passive"))
      (node (ref "C149") (pin "2") (pinfunction "2_2") (pintype "passive"))
      (node (ref "C151") (pin "2") (pinfunction "2_2") (pintype "passive"))
      (node (ref "C152") (pin "2") (pinfunction "2_2") (pintype "passive"))
      (node (ref "C153") (pin "2") (pinfunction "2_2") (pintype "passive"))
      (node (ref "C154") (pin "2") (pinfunction "2_2") (pintype "passive"))
      (node (ref "C155") (pin "2") (pinfunction "2_2") (pintype "passive"))
      (node (ref "C156") (pin "2") (pinfunction "2_2") (pintype "passive"))
      (node (ref "C160") (pin "2") (pinfunction "2_2") (pintype "passive"))
      (node (ref "C169") (pin "2") (pinfunction "2_2") (pintype "passive"))
      (node (ref "C177") (pin "2") (pinfunction "2_2") (pintype "passive"))
      (node (ref "C230") (pin "2") (pinfunction "2_2") (pintype "passive"))
      (node (ref "C231") (pin "2") (pinfunction "2_2") (pintype "passive"))
      (node (ref "C232") (pin "2") (pinfunction "2_2") (pintype "passive"))
      (node (ref "C233") (pin "2") (pinfunction "2_2") (pintype "passive"))
      (node (ref "C234") (pin "2") (pinfunction "2_2") (pintype "passive"))
      (node (ref "C235") (pin "2") (pinfunction "2_2") (pintype "passive"))
      (node (ref "C236") (pin "2") (pinfunction "2_2") (pintype "passive"))
      (node (ref "C237") (pin "2") (pinfunction "2_2") (pintype "passive"))
      (node (ref "C238") (pin "2") (pinfunction "2_2") (pintype "passive"))
      (node (ref "C239") (pin "2") (pinfunction "2_2") (pintype "passive"))
      (node (ref "C42") (pin "2") (pinfunction "2_2") (pintype "passive"))
      (node (ref "C44") (pin "2") (pinfunction "2_2") (pintype "passive"))
      (node (ref "C49") (pin "2") (pinfunction "2_2") (pintype "passive"))
      (node (ref "C74") (pin "2") (pinfunction "2_2") (pintype "passive"))
      (node (ref "IC2") (pin "AA11") (pinfunction "VCCO_2_AA11") (pintype "power_in"))
      (node (ref "IC2") (pin "AA15") (pinfunction "VCCO_2_AA15") (pintype "power_in"))
      (node (ref "IC2") (pin "AA19") (pinfunction "VCCO_2_AA19") (pintype "power_in"))
      (node (ref "IC2") (pin "AA7") (pinfunction "VCCO_2_AA7") (pintype "power_in"))
      (node (ref "IC2") (pin "AB3") (pinfunction "VCCO_2_AB3") (pintype "power_in"))
      (node (ref "IC2") (pin "B19") (pinfunction "VCCO_0_B19") (pintype "power_in"))
      (node (ref "IC2") (pin "B4") (pinfunction "VCCO_0_B4") (pintype "power_in"))
      (node (ref "IC2") (pin "E17") (pinfunction "VCCO_0_E17") (pintype "power_in"))
      (node (ref "IC2") (pin "F11") (pinfunction "VCCAUX_F11") (pintype "power_in"))
      (node (ref "IC2") (pin "F6") (pinfunction "VCCO_0_F6") (pintype "power_in"))
      (node (ref "IC2") (pin "G10") (pinfunction "VCCO_0_G10") (pintype "power_in"))
      (node (ref "IC2") (pin "G12") (pinfunction "VCCAUX_G12") (pintype "power_in"))
      (node (ref "IC2") (pin "G14") (pinfunction "VCCO_0_G14") (pintype "power_in"))
      (node (ref "IC2") (pin "H15") (pinfunction "VCCAUX_H15") (pintype "power_in"))
      (node (ref "IC2") (pin "H9") (pinfunction "VCCAUX_H9") (pintype "power_in"))
      (node (ref "IC2") (pin "K15") (pinfunction "VCCAUX_K15") (pintype "power_in"))
      (node (ref "IC2") (pin "L8") (pinfunction "VCCAUX_L8") (pintype "power_in"))
      (node (ref "IC2") (pin "M15") (pinfunction "VCCAUX_M15") (pintype "power_in"))
      (node (ref "IC2") (pin "N8") (pinfunction "VCCAUX_N8") (pintype "power_in"))
      (node (ref "IC2") (pin "R10") (pinfunction "VCCAUX_R10") (pintype "power_in"))
      (node (ref "IC2") (pin "R12") (pinfunction "VCCAUX_R12") (pintype "power_in"))
      (node (ref "IC2") (pin "R6") (pinfunction "VCCAUX_R6") (pintype "power_in"))
      (node (ref "IC2") (pin "T13") (pinfunction "VCCO_2_T13") (pintype "power_in"))
      (node (ref "IC2") (pin "T9") (pinfunction "VCCO_2_T9") (pintype "power_in"))
      (node (ref "IC2") (pin "U11") (pinfunction "VCCAUX_U11") (pintype "power_in"))
      (node (ref "IC2") (pin "V12") (pinfunction "VCCO_2_V12") (pintype "power_in"))
      (node (ref "IC2") (pin "V16") (pinfunction "VCCO_2_V16") (pintype "power_in"))
      (node (ref "IC2") (pin "V6") (pinfunction "VCCAUX_V6") (pintype "power_in"))
      (node (ref "IC2") (pin "V8") (pinfunction "VCCO_2_V8") (pintype "power_in"))
      (node (ref "IC2") (pin "W5") (pinfunction "VCCO_2_W5") (pintype "power_in"))
    )
  )
)
